# TapDriver-ESP32_schdoc_2022-04-13.net
KiCad netlist of a schematic drawn in Altium Designer
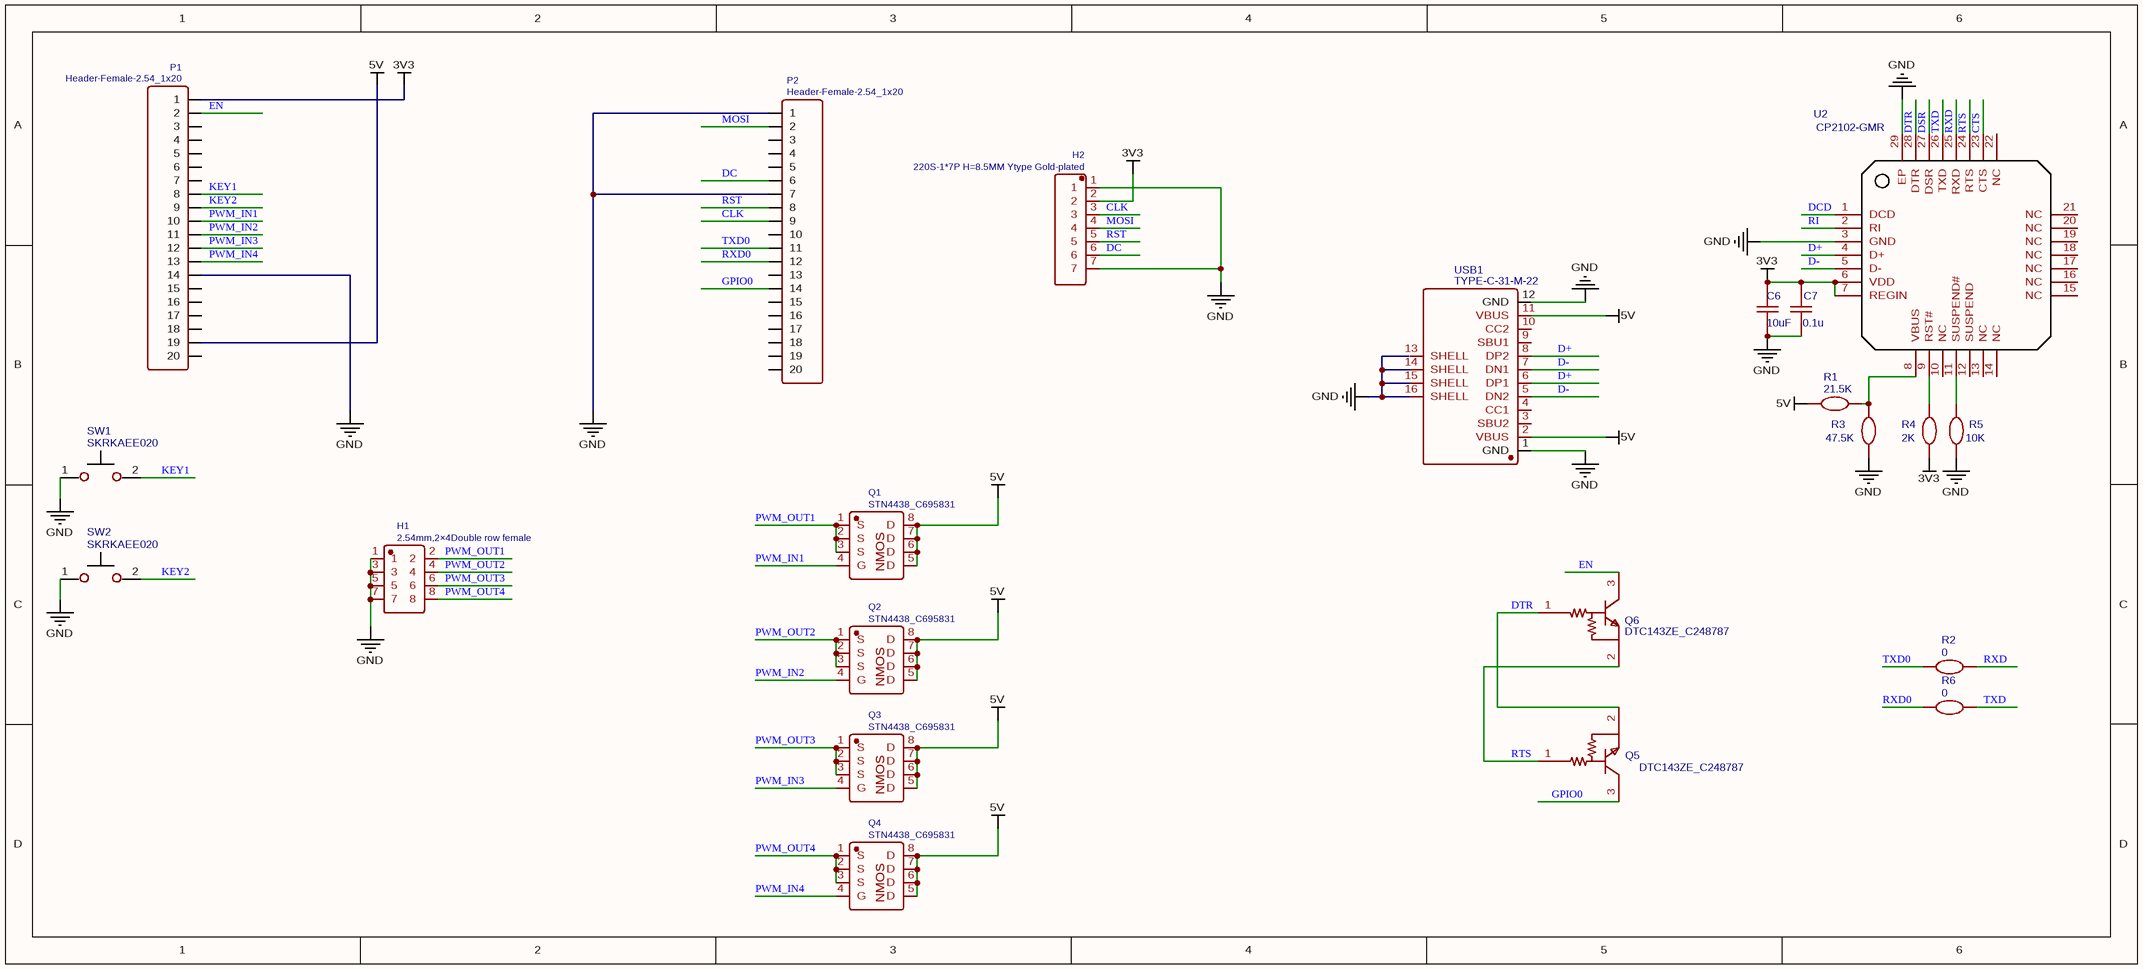
[diagram p0: TapDriver-ESP32.schdoc_2022-04-13.schdoc]

(export (version "E")
  (design (tool "Eeschema 10.0.6"))
  (components
    (comp (ref "C6")
      (value "10uF")
      (footprint "C0805")
      (fields (field (name "CONTRIBUTOR") "LCEDA_Lib"))
      (libsource (lib "altium-import") (part "root_1_10uF_"))
    )
    (comp (ref "C7")
      (value "0.1u")
      (footprint "C0603")
      (fields (field (name "CONTRIBUTOR") "LCEDA_Lib"))
      (libsource (lib "altium-import") (part "root_1_0.1u_"))
    )
    (comp (ref "H1")
      (value "2.54mm,2×4Double row female")
      (footprint "HDR-TH_8P-P2.54-V-F-R2-C4-S2.54-1")
      (fields (field (name "BOM_SUPPLIER PART") "C58378"))
      (libsource (lib "altium-import") (part "root_0_2.54mm,2×4Double row female_"))
    )
    (comp (ref "H2")
      (value "220S-1*7P H=8.5MM Ytype Gold-plated")
      (footprint "HDR-TH_7P-P2.54-V-F")
      (fields (field (name "BOM_SUPPLIER PART") "C124418") (field (name "CONTRIBUTOR") "LCSC"))
      (libsource (lib "altium-import") (part "root_0_220S-1*7P H=8.5MM Ytype Gold-plated_"))
    )
    (comp (ref "P1")
      (value "Header-Female-2.54_1x20")
      (footprint "HDR-TH_20P-P2.54-V-F")
      (fields
        (field (name "BOM_MANUFACTURER PART") "2.54mm 1*20P Female header")
        (field (name "BOM_SUPPLIER PART") "C50984")
      )
      (libsource (lib "altium-import") (part "root_0_Header-Female-2.54_1x20_"))
    )
    (comp (ref "P2")
      (value "Header-Female-2.54_1x20")
      (footprint "HDR-TH_20P-P2.54-V-F")
      (fields
        (field (name "BOM_MANUFACTURER PART") "2.54mm 1*20P Female header")
        (field (name "BOM_SUPPLIER PART") "C50984")
      )
      (libsource (lib "") (part "root_0_Header-Female-2.54_1x20__1"))
    )
    (comp (ref "Q1")
      (value "STN4438_C695831")
      (footprint "SOP-8_L4.9-W3.9-P1.27-LS6.0-BL")
      (fields
        (field (name "BOM_SUPPLIER PART") "C695831")
        (field (name "BOM_MANUFACTURER PART") "STN4438")
        (field (name "CONTRIBUTOR") "LCSC")
      )
      (libsource (lib "altium-import") (part "root_0_STN4438_C695831_"))
    )
    (comp (ref "Q2")
      (value "STN4438_C695831")
      (footprint "SOP-8_L4.9-W3.9-P1.27-LS6.0-BL")
      (fields
        (field (name "BOM_SUPPLIER PART") "C695831")
        (field (name "BOM_MANUFACTURER PART") "STN4438")
        (field (name "CONTRIBUTOR") "LCSC")
      )
      (libsource (lib "altium-import") (part "root_0_STN4438_C695831_"))
    )
    (comp (ref "Q3")
      (value "STN4438_C695831")
      (footprint "SOP-8_L4.9-W3.9-P1.27-LS6.0-BL")
      (fields
        (field (name "BOM_SUPPLIER PART") "C695831")
        (field (name "BOM_MANUFACTURER PART") "STN4438")
        (field (name "CONTRIBUTOR") "LCSC")
      )
      (libsource (lib "altium-import") (part "root_0_STN4438_C695831_"))
    )
    (comp (ref "Q4")
      (value "STN4438_C695831")
      (footprint "SOP-8_L4.9-W3.9-P1.27-LS6.0-BL")
      (fields
        (field (name "BOM_SUPPLIER PART") "C695831")
        (field (name "BOM_MANUFACTURER PART") "STN4438")
        (field (name "CONTRIBUTOR") "LCSC")
      )
      (libsource (lib "altium-import") (part "root_0_STN4438_C695831_"))
    )
    (comp (ref "Q5")
      (value "DTC143ZE_C248787")
      (footprint "SOT-523-3_L1.6-W0.8-P1.00-LS1.6-BR")
      (fields
        (field (name "BOM_SUPPLIER PART") "C248787")
        (field (name "BOM_MANUFACTURER PART") "DTC143ZE")
        (field (name "CONTRIBUTOR") "LCSC")
      )
      (libsource (lib "altium-import") (part "root_2_DTC143ZE_C248787_"))
    )
    (comp (ref "Q6")
      (value "DTC143ZE_C248787")
      (footprint "SOT-523-3_L1.6-W0.8-P1.00-LS1.6-BR")
      (fields
        (field (name "BOM_SUPPLIER PART") "C248787")
        (field (name "BOM_MANUFACTURER PART") "DTC143ZE")
        (field (name "CONTRIBUTOR") "LCSC")
      )
      (libsource (lib "altium-import") (part "root_0_DTC143ZE_C248787_"))
    )
    (comp (ref "R1")
      (value "21.5K")
      (footprint "R0603")
      (fields (field (name "CONTRIBUTOR") "LCEDA_Lib"))
      (libsource (lib "altium-import") (part "root_2_21.5K_"))
    )
    (comp (ref "R2")
      (value "0")
      (footprint "R0603")
      (fields (field (name "CONTRIBUTOR") "LCEDA_Lib"))
      (libsource (lib "altium-import") (part "root_2_0_"))
    )
    (comp (ref "R3")
      (value "47.5K")
      (footprint "R0603")
      (fields (field (name "CONTRIBUTOR") "LCEDA_Lib"))
      (libsource (lib "altium-import") (part "root_1_47.5K_"))
    )
    (comp (ref "R4")
      (value "2K")
      (footprint "R0603")
      (fields (field (name "CONTRIBUTOR") "LCEDA_Lib"))
      (libsource (lib "altium-import") (part "root_1_2K_"))
    )
    (comp (ref "R5")
      (value "10K")
      (footprint "R0603")
      (fields (field (name "CONTRIBUTOR") "LCEDA_Lib"))
      (libsource (lib "altium-import") (part "root_1_10K_"))
    )
    (comp (ref "R6")
      (value "0")
      (footprint "R0603")
      (fields (field (name "CONTRIBUTOR") "LCEDA_Lib"))
      (libsource (lib "altium-import") (part "root_2_0_"))
    )
    (comp (ref "SW1")
      (value "SKRKAEE020")
      (footprint "SKRKAEE020")
      (fields (field (name "BOM_SUPPLIER PART") "C115357"))
      (libsource (lib "altium-import") (part "root_0_SKRKAEE020_"))
    )
    (comp (ref "SW2")
      (value "SKRKAEE020")
      (footprint "SKRKAEE020")
      (fields (field (name "BOM_SUPPLIER PART") "C115357"))
      (libsource (lib "altium-import") (part "root_0_SKRKAEE020_"))
    )
    (comp (ref "U2")
      (value "CP2102-GMR")
      (footprint "QFN-28_L5.0-W5.0-P0.50-BL-EP")
      (fields (field (name "BOM_SUPPLIER PART") "C6568"))
      (libsource (lib "altium-import") (part "root_0_CP2102-GMR_"))
    )
    (comp (ref "USB1")
      (value "TYPE-C-31-M-22")
      (footprint "USB-C-SMD_TYPE-C-31-M-22")
      (fields (field (name "BOM_SUPPLIER PART") "C530612") (field (name "CONTRIBUTOR") "LCSC"))
      (libsource (lib "altium-import") (part "root_2_TYPE-C-31-M-22_"))
    )
  )
  (nets
    (net (code "1") (name "/CLK") (class "Default")
      (node (ref "H2") (pin "3") (pinfunction "3_3") (pintype "passive"))
      (node (ref "P2") (pin "9") (pinfunction "9_9") (pintype "passive"))
    )
    (net (code "2") (name "/CTS") (class "Default")
      (node (ref "U2") (pin "23") (pinfunction "CTS_23") (pintype "passive"))
    )
    (net (code "3") (name "/D+") (class "Default")
      (node (ref "U2") (pin "4") (pinfunction "D+_4") (pintype "passive"))
      (node (ref "USB1") (pin "6") (pinfunction "DP1_6") (pintype "passive"))
      (node (ref "USB1") (pin "8") (pinfunction "DP2_8") (pintype "passive"))
    )
    (net (code "4") (name "/D-") (class "Default")
      (node (ref "U2") (pin "5") (pinfunction "D-_5") (pintype "passive"))
      (node (ref "USB1") (pin "5") (pinfunction "DN2_5") (pintype "passive"))
      (node (ref "USB1") (pin "7") (pinfunction "DN1_7") (pintype "passive"))
    )
    (net (code "5") (name "/DC") (class "Default")
      (node (ref "H2") (pin "6") (pinfunction "6_6") (pintype "passive"))
      (node (ref "P2") (pin "6") (pinfunction "6_6") (pintype "passive"))
    )
    (net (code "6") (name "/DCD") (class "Default")
      (node (ref "U2") (pin "1") (pinfunction "DCD_1") (pintype "passive"))
    )
    (net (code "7") (name "/DSR") (class "Default")
      (node (ref "U2") (pin "27") (pinfunction "DSR_27") (pintype "passive"))
    )
    (net (code "8") (name "/DTR") (class "Default")
      (node (ref "Q5") (pin "2") (pinfunction "E_2") (pintype "passive"))
      (node (ref "Q6") (pin "1") (pinfunction "B_1") (pintype "passive"))
      (node (ref "U2") (pin "28") (pinfunction "DTR_28") (pintype "passive"))
    )
    (net (code "9") (name "/EN") (class "Default")
      (node (ref "P1") (pin "2") (pinfunction "2_2") (pintype "passive"))
      (node (ref "Q6") (pin "3") (pinfunction "C_3") (pintype "passive"))
    )
    (net (code "10") (name "/GPIO0") (class "Default")
      (node (ref "P2") (pin "14") (pinfunction "14_14") (pintype "passive"))
      (node (ref "Q5") (pin "3") (pinfunction "C_3") (pintype "passive"))
    )
    (net (code "11") (name "/KEY1") (class "Default")
      (node (ref "P1") (pin "8") (pinfunction "8_8") (pintype "passive"))
      (node (ref "SW1") (pin "2") (pinfunction "2_2") (pintype "passive"))
    )
    (net (code "12") (name "/KEY2") (class "Default")
      (node (ref "P1") (pin "9") (pinfunction "9_9") (pintype "passive"))
      (node (ref "SW2") (pin "2") (pinfunction "2_2") (pintype "passive"))
    )
    (net (code "13") (name "/MOSI") (class "Default")
      (node (ref "H2") (pin "4") (pinfunction "4_4") (pintype "passive"))
      (node (ref "P2") (pin "2") (pinfunction "2_2") (pintype "passive"))
    )
    (net (code "14") (name "/PWM_IN1") (class "Default")
      (node (ref "P1") (pin "10") (pinfunction "10_10") (pintype "passive"))
      (node (ref "Q1") (pin "4") (pinfunction "G_4") (pintype "passive"))
    )
    (net (code "15") (name "/PWM_IN2") (class "Default")
      (node (ref "P1") (pin "11") (pinfunction "11_11") (pintype "passive"))
      (node (ref "Q2") (pin "4") (pinfunction "G_4") (pintype "passive"))
    )
    (net (code "16") (name "/PWM_IN3") (class "Default")
      (node (ref "P1") (pin "12") (pinfunction "12_12") (pintype "passive"))
      (node (ref "Q3") (pin "4") (pinfunction "G_4") (pintype "passive"))
    )
    (net (code "17") (name "/PWM_IN4") (class "Default")
      (node (ref "P1") (pin "13") (pinfunction "13_13") (pintype "passive"))
      (node (ref "Q4") (pin "4") (pinfunction "G_4") (pintype "passive"))
    )
    (net (code "18") (name "/PWM_OUT1") (class "Default")
      (node (ref "H1") (pin "2") (pinfunction "2_2") (pintype "passive"))
      (node (ref "Q1") (pin "1") (pinfunction "S_1") (pintype "passive"))
      (node (ref "Q1") (pin "2") (pinfunction "S_2") (pintype "passive"))
      (node (ref "Q1") (pin "3") (pinfunction "S_3") (pintype "passive"))
    )
    (net (code "19") (name "/PWM_OUT2") (class "Default")
      (node (ref "H1") (pin "4") (pinfunction "4_4") (pintype "passive"))
      (node (ref "Q2") (pin "1") (pinfunction "S_1") (pintype "passive"))
      (node (ref "Q2") (pin "2") (pinfunction "S_2") (pintype "passive"))
      (node (ref "Q2") (pin "3") (pinfunction "S_3") (pintype "passive"))
    )
    (net (code "20") (name "/PWM_OUT3") (class "Default")
      (node (ref "H1") (pin "6") (pinfunction "6_6") (pintype "passive"))
      (node (ref "Q3") (pin "1") (pinfunction "S_1") (pintype "passive"))
      (node (ref "Q3") (pin "2") (pinfunction "S_2") (pintype "passive"))
      (node (ref "Q3") (pin "3") (pinfunction "S_3") (pintype "passive"))
    )
    (net (code "21") (name "/PWM_OUT4") (class "Default")
      (node (ref "H1") (pin "8") (pinfunction "8_8") (pintype "passive"))
      (node (ref "Q4") (pin "1") (pinfunction "S_1") (pintype "passive"))
      (node (ref "Q4") (pin "2") (pinfunction "S_2") (pintype "passive"))
      (node (ref "Q4") (pin "3") (pinfunction "S_3") (pintype "passive"))
    )
    (net (code "22") (name "/RI") (class "Default")
      (node (ref "U2") (pin "2") (pinfunction "RI_2") (pintype "passive"))
    )
    (net (code "23") (name "/RST") (class "Default")
      (node (ref "H2") (pin "5") (pinfunction "5_5") (pintype "passive"))
      (node (ref "P2") (pin "8") (pinfunction "8_8") (pintype "passive"))
    )
    (net (code "24") (name "/RTS") (class "Default")
      (node (ref "Q5") (pin "1") (pinfunction "B_1") (pintype "passive"))
      (node (ref "Q6") (pin "2") (pinfunction "E_2") (pintype "passive"))
      (node (ref "U2") (pin "24") (pinfunction "RTS_24") (pintype "passive"))
    )
    (net (code "25") (name "/RXD") (class "Default")
      (node (ref "R2") (pin "1") (pinfunction "1_1") (pintype "passive"))
      (node (ref "U2") (pin "25") (pinfunction "RXD_25") (pintype "passive"))
    )
    (net (code "26") (name "/RXD0") (class "Default")
      (node (ref "P2") (pin "12") (pinfunction "12_12") (pintype "passive"))
      (node (ref "R6") (pin "2") (pinfunction "2_2") (pintype "passive"))
    )
    (net (code "27") (name "/TXD") (class "Default")
      (node (ref "R6") (pin "1") (pinfunction "1_1") (pintype "passive"))
      (node (ref "U2") (pin "26") (pinfunction "TXD_26") (pintype "passive"))
    )
    (net (code "28") (name "/TXD0") (class "Default")
      (node (ref "P2") (pin "11") (pinfunction "11_11") (pintype "passive"))
      (node (ref "R2") (pin "2") (pinfunction "2_2") (pintype "passive"))
    )
    (net (code "29") (name "3V3") (class "Default")
      (node (ref "C6") (pin "2") (pinfunction "2_2") (pintype "passive"))
      (node (ref "C7") (pin "2") (pinfunction "2_2") (pintype "passive"))
      (node (ref "H2") (pin "2") (pinfunction "2_2") (pintype "passive"))
      (node (ref "P1") (pin "1") (pinfunction "1_1") (pintype "passive"))
      (node (ref "R4") (pin "1") (pinfunction "1_1") (pintype "passive"))
      (node (ref "U2") (pin "6") (pinfunction "VDD_6") (pintype "passive"))
      (node (ref "U2") (pin "7") (pinfunction "REGIN_7") (pintype "passive"))
    )
    (net (code "30") (name "5V") (class "Default")
      (node (ref "P1") (pin "19") (pinfunction "19_19") (pintype "passive"))
      (node (ref "Q1") (pin "5") (pinfunction "D_5") (pintype "passive"))
      (node (ref "Q1") (pin "6") (pinfunction "D_6") (pintype "passive"))
      (node (ref "Q1") (pin "7") (pinfunction "D_7") (pintype "passive"))
      (node (ref "Q1") (pin "8") (pinfunction "D_8") (pintype "passive"))
      (node (ref "Q2") (pin "5") (pinfunction "D_5") (pintype "passive"))
      (node (ref "Q2") (pin "6") (pinfunction "D_6") (pintype "passive"))
      (node (ref "Q2") (pin "7") (pinfunction "D_7") (pintype "passive"))
      (node (ref "Q2") (pin "8") (pinfunction "D_8") (pintype "passive"))
      (node (ref "Q3") (pin "5") (pinfunction "D_5") (pintype "passive"))
      (node (ref "Q3") (pin "6") (pinfunction "D_6") (pintype "passive"))
      (node (ref "Q3") (pin "7") (pinfunction "D_7") (pintype "passive"))
      (node (ref "Q3") (pin "8") (pinfunction "D_8") (pintype "passive"))
      (node (ref "Q4") (pin "5") (pinfunction "D_5") (pintype "passive"))
      (node (ref "Q4") (pin "6") (pinfunction "D_6") (pintype "passive"))
      (node (ref "Q4") (pin "7") (pinfunction "D_7") (pintype "passive"))
      (node (ref "Q4") (pin "8") (pinfunction "D_8") (pintype "passive"))
      (node (ref "R1") (pin "2") (pinfunction "2_2") (pintype "passive"))
      (node (ref "USB1") (pin "11") (pinfunction "VBUS_11") (pintype "passive"))
      (node (ref "USB1") (pin "2") (pinfunction "VBUS_2") (pintype "passive"))
    )
    (net (code "31") (name "GND") (class "Default")
      (node (ref "C6") (pin "1") (pinfunction "1_1") (pintype "passive"))
      (node (ref "C7") (pin "1") (pinfunction "1_1") (pintype "passive"))
      (node (ref "H1") (pin "1") (pinfunction "1_1") (pintype "passive"))
      (node (ref "H1") (pin "3") (pinfunction "3_3") (pintype "passive"))
      (node (ref "H1") (pin "5") (pinfunction "5_5") (pintype "passive"))
      (node (ref "H1") (pin "7") (pinfunction "7_7") (pintype "passive"))
      (node (ref "H2") (pin "1") (pinfunction "1_1") (pintype "passive"))
      (node (ref "H2") (pin "7") (pinfunction "7_7") (pintype "passive"))
      (node (ref "P1") (pin "14") (pinfunction "14_14") (pintype "passive"))
      (node (ref "P2") (pin "1") (pinfunction "1_1") (pintype "passive"))
      (node (ref "P2") (pin "7") (pinfunction "7_7") (pintype "passive"))
      (node (ref "R3") (pin "1") (pinfunction "1_1") (pintype "passive"))
      (node (ref "R5") (pin "1") (pinfunction "1_1") (pintype "passive"))
      (node (ref "SW1") (pin "1") (pinfunction "1_1") (pintype "passive"))
      (node (ref "SW2") (pin "1") (pinfunction "1_1") (pintype "passive"))
      (node (ref "U2") (pin "29") (pinfunction "EP_29") (pintype "passive"))
      (node (ref "U2") (pin "3") (pinfunction "GND_3") (pintype "passive"))
      (node (ref "USB1") (pin "1") (pinfunction "GND_1") (pintype "passive"))
      (node (ref "USB1") (pin "12") (pinfunction "GND_12") (pintype "passive"))
      (node (ref "USB1") (pin "14") (pinfunction "SHELL_14") (pintype "passive"))
      (node (ref "USB1") (pin "15") (pinfunction "SHELL_15") (pintype "passive"))
      (node (ref "USB1") (pin "16") (pinfunction "SHELL_16") (pintype "passive"))
    )
    (net (code "32") (name "Net-(U2-RST#)") (class "Default")
      (node (ref "R4") (pin "2") (pinfunction "2_2") (pintype "passive"))
      (node (ref "U2") (pin "9") (pinfunction "RST#_9") (pintype "passive"))
    )
    (net (code "33") (name "Net-(U2-SUSPEND#)") (class "Default")
      (node (ref "R5") (pin "2") (pinfunction "2_2") (pintype "passive"))
      (node (ref "U2") (pin "11") (pinfunction "SUSPEND#_11") (pintype "passive"))
    )
    (net (code "34") (name "Net-(U2-VBUS)") (class "Default")
      (node (ref "R1") (pin "1") (pinfunction "1_1") (pintype "passive"))
      (node (ref "R3") (pin "2") (pinfunction "2_2") (pintype "passive"))
      (node (ref "U2") (pin "8") (pinfunction "VBUS_8") (pintype "passive"))
    )
    (net (code "35") (name "unconnected-(P1-Pad3)") (class "Default")
      (node (ref "P1") (pin "3") (pinfunction "3_3") (pintype "passive"))
    )
    (net (code "36") (name "unconnected-(P1-Pad4)") (class "Default")
      (node (ref "P1") (pin "4") (pinfunction "4_4") (pintype "passive"))
    )
    (net (code "37") (name "unconnected-(P1-Pad5)") (class "Default")
      (node (ref "P1") (pin "5") (pinfunction "5_5") (pintype "passive"))
    )
    (net (code "38") (name "unconnected-(P1-Pad6)") (class "Default")
      (node (ref "P1") (pin "6") (pinfunction "6_6") (pintype "passive"))
    )
    (net (code "39") (name "unconnected-(P1-Pad7)") (class "Default")
      (node (ref "P1") (pin "7") (pinfunction "7_7") (pintype "passive"))
    )
    (net (code "40") (name "unconnected-(P1-Pad15)") (class "Default")
      (node (ref "P1") (pin "15") (pinfunction "15_15") (pintype "passive"))
    )
    (net (code "41") (name "unconnected-(P1-Pad16)") (class "Default")
      (node (ref "P1") (pin "16") (pinfunction "16_16") (pintype "passive"))
    )
    (net (code "42") (name "unconnected-(P1-Pad17)") (class "Default")
      (node (ref "P1") (pin "17") (pinfunction "17_17") (pintype "passive"))
    )
    (net (code "43") (name "unconnected-(P1-Pad18)") (class "Default")
      (node (ref "P1") (pin "18") (pinfunction "18_18") (pintype "passive"))
    )
    (net (code "44") (name "unconnected-(P1-Pad20)") (class "Default")
      (node (ref "P1") (pin "20") (pinfunction "20_20") (pintype "passive"))
    )
    (net (code "45") (name "unconnected-(P2-Pad3)") (class "Default")
      (node (ref "P2") (pin "3") (pinfunction "3_3") (pintype "passive"))
    )
    (net (code "46") (name "unconnected-(P2-Pad4)") (class "Default")
      (node (ref "P2") (pin "4") (pinfunction "4_4") (pintype "passive"))
    )
    (net (code "47") (name "unconnected-(P2-Pad5)") (class "Default")
      (node (ref "P2") (pin "5") (pinfunction "5_5") (pintype "passive"))
    )
    (net (code "48") (name "unconnected-(P2-Pad10)") (class "Default")
      (node (ref "P2") (pin "10") (pinfunction "10_10") (pintype "passive"))
    )
    (net (code "49") (name "unconnected-(P2-Pad13)") (class "Default")
      (node (ref "P2") (pin "13") (pinfunction "13_13") (pintype "passive"))
    )
    (net (code "50") (name "unconnected-(P2-Pad15)") (class "Default")
      (node (ref "P2") (pin "15") (pinfunction "15_15") (pintype "passive"))
    )
    (net (code "51") (name "unconnected-(P2-Pad16)") (class "Default")
      (node (ref "P2") (pin "16") (pinfunction "16_16") (pintype "passive"))
    )
    (net (code "52") (name "unconnected-(P2-Pad17)") (class "Default")
      (node (ref "P2") (pin "17") (pinfunction "17_17") (pintype "passive"))
    )
    (net (code "53") (name "unconnected-(P2-Pad18)") (class "Default")
      (node (ref "P2") (pin "18") (pinfunction "18_18") (pintype "passive"))
    )
    (net (code "54") (name "unconnected-(P2-Pad19)") (class "Default")
      (node (ref "P2") (pin "19") (pinfunction "19_19") (pintype "passive"))
    )
    (net (code "55") (name "unconnected-(P2-Pad20)") (class "Default")
      (node (ref "P2") (pin "20") (pinfunction "20_20") (pintype "passive"))
    )
    (net (code "56") (name "unconnected-(U2-NC-Pad10)") (class "Default")
      (node (ref "U2") (pin "10") (pinfunction "NC_10") (pintype "passive"))
    )
    (net (code "57") (name "unconnected-(U2-NC-Pad13)") (class "Default")
      (node (ref "U2") (pin "13") (pinfunction "NC_13") (pintype "passive"))
    )
    (net (code "58") (name "unconnected-(U2-NC-Pad14)") (class "Default")
      (node (ref "U2") (pin "14") (pinfunction "NC_14") (pintype "passive"))
    )
    (net (code "59") (name "unconnected-(U2-NC-Pad15)") (class "Default")
      (node (ref "U2") (pin "15") (pinfunction "NC_15") (pintype "passive"))
    )
    (net (code "60") (name "unconnected-(U2-NC-Pad16)") (class "Default")
      (node (ref "U2") (pin "16") (pinfunction "NC_16") (pintype "passive"))
    )
    (net (code "61") (name "unconnected-(U2-NC-Pad17)") (class "Default")
      (node (ref "U2") (pin "17") (pinfunction "NC_17") (pintype "passive"))
    )
    (net (code "62") (name "unconnected-(U2-NC-Pad18)") (class "Default")
      (node (ref "U2") (pin "18") (pinfunction "NC_18") (pintype "passive"))
    )
    (net (code "63") (name "unconnected-(U2-NC-Pad19)") (class "Default")
      (node (ref "U2") (pin "19") (pinfunction "NC_19") (pintype "passive"))
    )
    (net (code "64") (name "unconnected-(U2-NC-Pad20)") (class "Default")
      (node (ref "U2") (pin "20") (pinfunction "NC_20") (pintype "passive"))
    )
    (net (code "65") (name "unconnected-(U2-NC-Pad21)") (class "Default")
      (node (ref "U2") (pin "21") (pinfunction "NC_21") (pintype "passive"))
    )
    (net (code "66") (name "unconnected-(U2-NC-Pad22)") (class "Default")
      (node (ref "U2") (pin "22") (pinfunction "NC_22") (pintype "passive"))
    )
    (net (code "67") (name "unconnected-(U2-SUSPEND-Pad12)") (class "Default")
      (node (ref "U2") (pin "12") (pinfunction "SUSPEND_12") (pintype "passive"))
    )
    (net (code "68") (name "unconnected-(USB1-CC1-Pad4)") (class "Default")
      (node (ref "USB1") (pin "4") (pinfunction "CC1_4") (pintype "passive"))
    )
    (net (code "69") (name "unconnected-(USB1-CC2-Pad10)") (class "Default")
      (node (ref "USB1") (pin "10") (pinfunction "CC2_10") (pintype "passive"))
    )
    (net (code "70") (name "unconnected-(USB1-SBU1-Pad9)") (class "Default")
      (node (ref "USB1") (pin "9") (pinfunction "SBU1_9") (pintype "passive"))
    )
    (net (code "71") (name "unconnected-(USB1-SBU2-Pad3)") (class "Default")
      (node (ref "USB1") (pin "3") (pinfunction "SBU2_3") (pintype "passive"))
    )
    (net (code "72") (name "unconnected-(USB1-SHELL-Pad13)") (class "Default")
      (node (ref "USB1") (pin "13") (pinfunction "SHELL_13") (pintype "passive"))
    )
  )
)
